# MicroMultimeter_KEY_Sch.net
KiCad netlist of a schematic drawn in Altium Designer
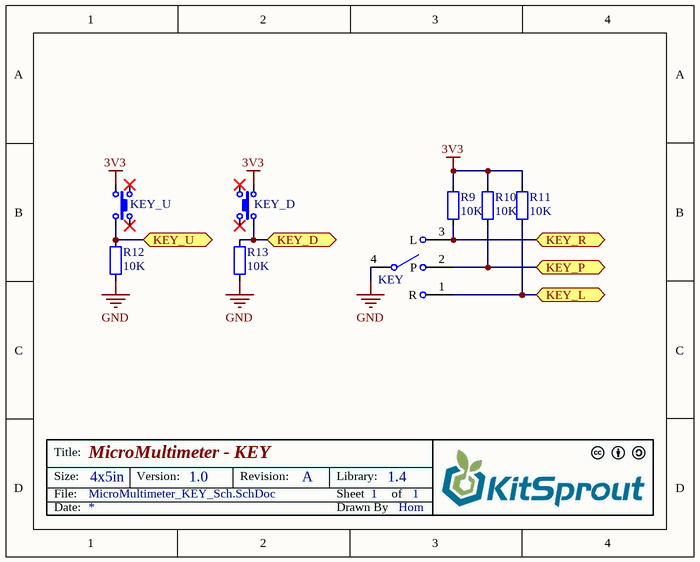
[diagram p0: MicroMultimeter_KEY_Sch.SchDoc]

(export (version "E")
  (design (tool "Eeschema 10.0.6"))
  (components
    (comp (ref "KEY")
      (value "ButtonPushLever_11*12_90")
      (footprint "PCB_Switch:ButtonPushLever_11*12_90")
      (description "Button")
      (libsource (lib "SCH_Switch") (part "ButtonPushLever_11*12_90"))
    )
    (comp (ref "KEY_D")
      (value "ButtonTACT")
      (footprint "PCB_Switch:ButtonTACT_3.5*3.55_90")
      (description "Button")
      (libsource (lib "SCH_Switch") (part "ButtonTACT"))
    )
    (comp (ref "KEY_U")
      (value "ButtonTACT")
      (footprint "PCB_Switch:ButtonTACT_3.5*3.55_90")
      (description "Button")
      (libsource (lib "SCH_Switch") (part "ButtonTACT"))
    )
    (comp (ref "R9")
      (value "10K")
      (footprint "PCB_PassiveRes:RES_0603")
      (description "Resistor")
      (fields (field (name "Comment") "Res_0603"))
      (libsource (lib "SCH_Passive") (part "Res_0603"))
    )
    (comp (ref "R10")
      (value "10K")
      (footprint "PCB_PassiveRes:RES_0603")
      (description "Resistor")
      (fields (field (name "Comment") "Res_0603"))
      (libsource (lib "SCH_Passive") (part "Res_0603"))
    )
    (comp (ref "R11")
      (value "10K")
      (footprint "PCB_PassiveRes:RES_0603")
      (description "Resistor")
      (fields (field (name "Comment") "Res_0603"))
      (libsource (lib "SCH_Passive") (part "Res_0603"))
    )
    (comp (ref "R12")
      (value "10K")
      (footprint "PCB_PassiveRes:RES_0603")
      (description "Resistor")
      (fields (field (name "Comment") "Res_0603"))
      (libsource (lib "SCH_Passive") (part "Res_0603"))
    )
    (comp (ref "R13")
      (value "10K")
      (footprint "PCB_PassiveRes:RES_0603")
      (description "Resistor")
      (fields (field (name "Comment") "Res_0603"))
      (libsource (lib "SCH_Passive") (part "Res_0603"))
    )
  )
  (nets
    (net (code "1") (name "/KEY_D") (class "Default")
      (node (ref "KEY_D") (pin "3") (pinfunction "3_3") (pintype "passive"))
      (node (ref "R13") (pin "2") (pinfunction "2_2") (pintype "passive"))
    )
    (net (code "2") (name "/KEY_L") (class "Default")
      (node (ref "KEY") (pin "1") (pinfunction "R_1") (pintype "passive"))
      (node (ref "R11") (pin "1") (pinfunction "1_1") (pintype "passive"))
    )
    (net (code "3") (name "/KEY_P") (class "Default")
      (node (ref "KEY") (pin "2") (pinfunction "P_2") (pintype "passive"))
      (node (ref "R10") (pin "1") (pinfunction "1_1") (pintype "passive"))
    )
    (net (code "4") (name "/KEY_R") (class "Default")
      (node (ref "KEY") (pin "3") (pinfunction "L_3") (pintype "passive"))
      (node (ref "R9") (pin "1") (pinfunction "1_1") (pintype "passive"))
    )
    (net (code "5") (name "/KEY_U") (class "Default")
      (node (ref "KEY_U") (pin "4") (pinfunction "4_4") (pintype "passive"))
      (node (ref "R12") (pin "2") (pinfunction "2_2") (pintype "passive"))
    )
    (net (code "6") (name "3V3") (class "Default")
      (node (ref "KEY_D") (pin "4") (pinfunction "4_4") (pintype "passive"))
      (node (ref "KEY_U") (pin "3") (pinfunction "3_3") (pintype "passive"))
      (node (ref "R10") (pin "2") (pinfunction "2_2") (pintype "passive"))
      (node (ref "R11") (pin "2") (pinfunction "2_2") (pintype "passive"))
      (node (ref "R9") (pin "2") (pinfunction "2_2") (pintype "passive"))
    )
    (net (code "7") (name "GND") (class "Default")
      (node (ref "KEY") (pin "4") (pinfunction "4_4") (pintype "passive"))
      (node (ref "R12") (pin "1") (pinfunction "1_1") (pintype "passive"))
      (node (ref "R13") (pin "1") (pinfunction "1_1") (pintype "passive"))
    )
    (net (code "8") (name "unconnected-(KEY_D-Pad1)") (class "Default")
      (node (ref "KEY_D") (pin "1") (pinfunction "1_1") (pintype "passive+no_connect"))
    )
    (net (code "9") (name "unconnected-(KEY_D-Pad2)") (class "Default")
      (node (ref "KEY_D") (pin "2") (pinfunction "2_2") (pintype "passive+no_connect"))
    )
    (net (code "10") (name "unconnected-(KEY_U-Pad1)") (class "Default")
      (node (ref "KEY_U") (pin "1") (pinfunction "1_1") (pintype "passive+no_connect"))
    )
    (net (code "11") (name "unconnected-(KEY_U-Pad2)") (class "Default")
      (node (ref "KEY_U") (pin "2") (pinfunction "2_2") (pintype "passive+no_connect"))
    )
  )
)
